# SensorBoard.net
KiCad netlist of a schematic drawn in EAGLE
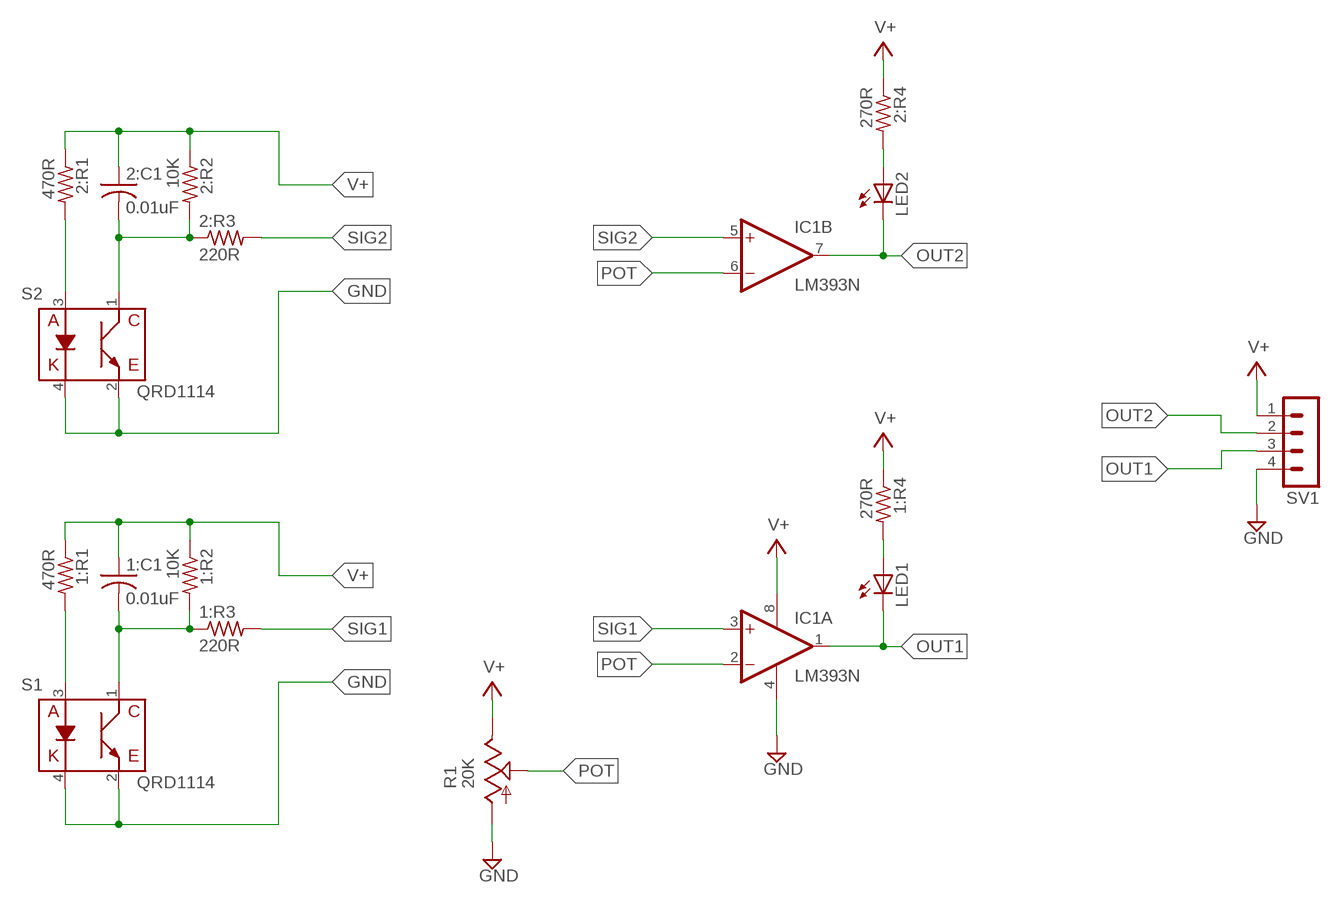
[diagram p0: schematic, sheet 1]

(export (version "E")
  (design (tool "Eeschema 10.0.6"))
  (components
    (comp (ref "1:C1")
      (value "0.01uF")
      (footprint "eagle-import:C025-025X050")
      (libsource (lib "eagle-import") (part "C-US025-025X050"))
    )
    (comp (ref "1:R1")
      (value "470R")
      (footprint "eagle-import:0207_12")
      (libsource (lib "eagle-import") (part "R-US_0207/12"))
    )
    (comp (ref "1:R2")
      (value "10K")
      (footprint "eagle-import:0207_12")
      (libsource (lib "eagle-import") (part "R-US_0207/12"))
    )
    (comp (ref "1:R3")
      (value "220R")
      (footprint "eagle-import:0207_10")
      (libsource (lib "eagle-import") (part "R-US_0207/10"))
    )
    (comp (ref "1:R4")
      (value "270R")
      (footprint "eagle-import:0207_12")
      (libsource (lib "eagle-import") (part "R-US_0207/12"))
    )
    (comp (ref "2:C1")
      (value "0.01uF")
      (footprint "eagle-import:C025-025X050")
      (libsource (lib "eagle-import") (part "C-US025-025X050"))
    )
    (comp (ref "2:R1")
      (value "470R")
      (footprint "eagle-import:0207_12")
      (libsource (lib "eagle-import") (part "R-US_0207/12"))
    )
    (comp (ref "2:R2")
      (value "10K")
      (footprint "eagle-import:0207_12")
      (libsource (lib "eagle-import") (part "R-US_0207/12"))
    )
    (comp (ref "2:R3")
      (value "220R")
      (footprint "eagle-import:0207_10")
      (libsource (lib "eagle-import") (part "R-US_0207/10"))
    )
    (comp (ref "2:R4")
      (value "270R")
      (footprint "eagle-import:0207_12")
      (libsource (lib "eagle-import") (part "R-US_0207/12"))
    )
    (comp (ref "IC1")
      (value "LM393N")
      (footprint "eagle-import:DIL08")
      (libsource (lib "eagle-import") (part "LM393N"))
    )
    (comp (ref "LED1")
      (value "LED5MM")
      (footprint "eagle-import:LED5MM")
      (libsource (lib "eagle-import") (part "LED5MM"))
    )
    (comp (ref "LED2")
      (value "LED5MM")
      (footprint "eagle-import:LED5MM")
      (libsource (lib "eagle-import") (part "LED5MM"))
    )
    (comp (ref "R1")
      (value "20K")
      (footprint "eagle-import:B25P")
      (libsource (lib "eagle-import") (part "TRIM_US-B25P"))
    )
    (comp (ref "S1")
      (value "QRD1114")
      (footprint "eagle-import:QRD1114")
      (libsource (lib "eagle-import") (part "QRD1114"))
    )
    (comp (ref "S2")
      (value "QRD1114")
      (footprint "eagle-import:QRD1114")
      (libsource (lib "eagle-import") (part "QRD1114"))
    )
    (comp (ref "SV1")
      (value "MA04-1")
      (footprint "eagle-import:MA04-1")
      (libsource (lib "eagle-import") (part "MA04-1"))
    )
  )
  (nets
    (net (code "1") (name "GND") (class "Default")
      (node (ref "IC1") (pin "4") (pinfunction "V-_4") (pintype "power_in"))
      (node (ref "R1") (pin "A") (pinfunction "A_A") (pintype "passive"))
      (node (ref "S1") (pin "2") (pinfunction "C_2") (pintype "bidirectional"))
      (node (ref "S1") (pin "4") (pinfunction "K_4") (pintype "bidirectional"))
      (node (ref "S2") (pin "2") (pinfunction "C_2") (pintype "bidirectional"))
      (node (ref "S2") (pin "4") (pinfunction "K_4") (pintype "bidirectional"))
      (node (ref "SV1") (pin "4") (pinfunction "4_4") (pintype "passive"))
    )
    (net (code "2") (name "Net-(1:R4-Pad2)") (class "Default")
      (node (ref "1:R4") (pin "2") (pinfunction "2_2") (pintype "passive"))
      (node (ref "LED1") (pin "A") (pinfunction "A_A") (pintype "passive"))
    )
    (net (code "3") (name "Net-(2:R4-Pad2)") (class "Default")
      (node (ref "2:R4") (pin "2") (pinfunction "2_2") (pintype "passive"))
      (node (ref "LED2") (pin "A") (pinfunction "A_A") (pintype "passive"))
    )
    (net (code "4") (name "Net-(S1-A)") (class "Default")
      (node (ref "1:R1") (pin "2") (pinfunction "2_2") (pintype "passive"))
      (node (ref "S1") (pin "3") (pinfunction "A_3") (pintype "bidirectional"))
    )
    (net (code "5") (name "Net-(S1-E)") (class "Default")
      (node (ref "1:C1") (pin "2") (pinfunction "2_2") (pintype "passive"))
      (node (ref "1:R2") (pin "2") (pinfunction "2_2") (pintype "passive"))
      (node (ref "1:R3") (pin "1") (pinfunction "1_1") (pintype "passive"))
      (node (ref "S1") (pin "1") (pinfunction "E_1") (pintype "bidirectional"))
    )
    (net (code "6") (name "Net-(S2-A)") (class "Default")
      (node (ref "2:R1") (pin "2") (pinfunction "2_2") (pintype "passive"))
      (node (ref "S2") (pin "3") (pinfunction "A_3") (pintype "bidirectional"))
    )
    (net (code "7") (name "Net-(S2-E)") (class "Default")
      (node (ref "2:C1") (pin "2") (pinfunction "2_2") (pintype "passive"))
      (node (ref "2:R2") (pin "2") (pinfunction "2_2") (pintype "passive"))
      (node (ref "2:R3") (pin "1") (pinfunction "1_1") (pintype "passive"))
      (node (ref "S2") (pin "1") (pinfunction "E_1") (pintype "bidirectional"))
    )
    (net (code "8") (name "OUT1") (class "Default")
      (node (ref "IC1") (pin "1") (pinfunction "OUT_1") (pintype "output"))
      (node (ref "LED1") (pin "K") (pinfunction "C_K") (pintype "passive"))
      (node (ref "SV1") (pin "3") (pinfunction "3_3") (pintype "passive"))
    )
    (net (code "9") (name "OUT2") (class "Default")
      (node (ref "IC1") (pin "7") (pinfunction "OUT_7") (pintype "output"))
      (node (ref "LED2") (pin "K") (pinfunction "C_K") (pintype "passive"))
      (node (ref "SV1") (pin "2") (pinfunction "2_2") (pintype "passive"))
    )
    (net (code "10") (name "POT") (class "Default")
      (node (ref "IC1") (pin "2") (pinfunction "-IN_2") (pintype "input"))
      (node (ref "IC1") (pin "6") (pinfunction "-IN_6") (pintype "input"))
      (node (ref "R1") (pin "S") (pinfunction "S_S") (pintype "passive"))
    )
    (net (code "11") (name "SIG1") (class "Default")
      (node (ref "1:R3") (pin "2") (pinfunction "2_2") (pintype "passive"))
      (node (ref "IC1") (pin "3") (pinfunction "+IN_3") (pintype "input"))
    )
    (net (code "12") (name "SIG2") (class "Default")
      (node (ref "2:R3") (pin "2") (pinfunction "2_2") (pintype "passive"))
      (node (ref "IC1") (pin "5") (pinfunction "+IN_5") (pintype "input"))
    )
    (net (code "13") (name "V+") (class "Default")
      (node (ref "1:C1") (pin "1") (pinfunction "1_1") (pintype "passive"))
      (node (ref "1:R1") (pin "1") (pinfunction "1_1") (pintype "passive"))
      (node (ref "1:R2") (pin "1") (pinfunction "1_1") (pintype "passive"))
      (node (ref "1:R4") (pin "1") (pinfunction "1_1") (pintype "passive"))
      (node (ref "2:C1") (pin "1") (pinfunction "1_1") (pintype "passive"))
      (node (ref "2:R1") (pin "1") (pinfunction "1_1") (pintype "passive"))
      (node (ref "2:R2") (pin "1") (pinfunction "1_1") (pintype "passive"))
      (node (ref "2:R4") (pin "1") (pinfunction "1_1") (pintype "passive"))
      (node (ref "IC1") (pin "8") (pinfunction "V+_8") (pintype "power_in"))
      (node (ref "R1") (pin "E") (pinfunction "E_E") (pintype "passive"))
      (node (ref "SV1") (pin "1") (pinfunction "1_1") (pintype "passive"))
    )
  )
)
